# LC_Filter.net
KiCad netlist of a schematic drawn in EAGLE
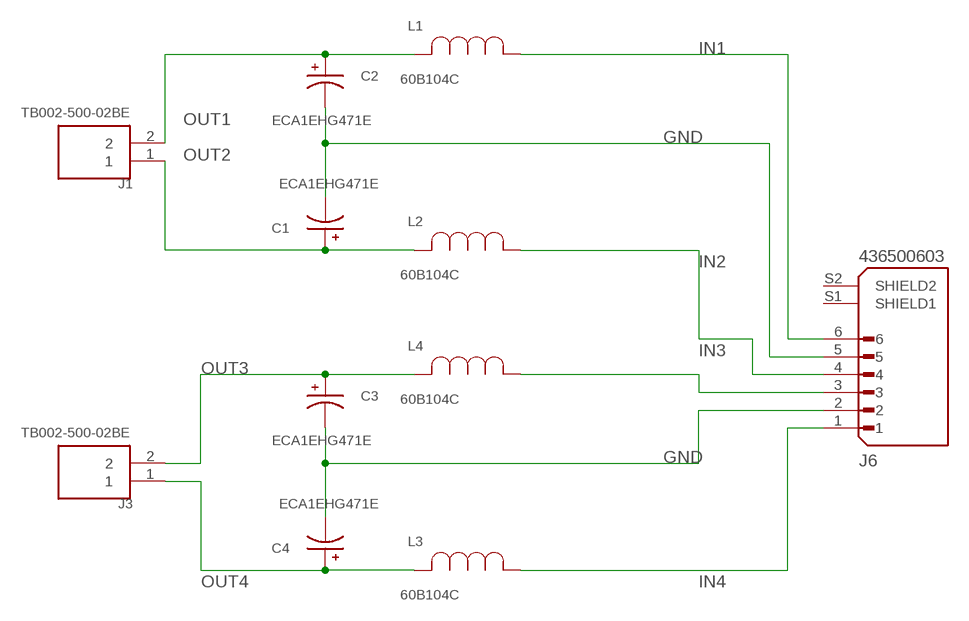
[diagram p0: schematic, sheet 1]

(export (version "E")
  (design (tool "Eeschema 10.0.6"))
  (components
    (comp (ref "C1")
      (value "ECA1EHG471E")
      (footprint "eagle-import:CAPPRD500W60D1000H1250")
      (fields (field (name "MF") "PANASONIC"))
      (libsource (lib "eagle-import") (part "ECA1EHG471E"))
    )
    (comp (ref "C2")
      (value "ECA1EHG471E")
      (footprint "eagle-import:CAPPRD500W60D1000H1250")
      (fields (field (name "MF") "PANASONIC"))
      (libsource (lib "eagle-import") (part "ECA1EHG471E"))
    )
    (comp (ref "C3")
      (value "ECA1EHG471E")
      (footprint "eagle-import:CAPPRD500W60D1000H1250")
      (fields (field (name "MF") "PANASONIC"))
      (libsource (lib "eagle-import") (part "ECA1EHG471E"))
    )
    (comp (ref "C4")
      (value "ECA1EHG471E")
      (footprint "eagle-import:CAPPRD500W60D1000H1250")
      (fields (field (name "MF") "PANASONIC"))
      (libsource (lib "eagle-import") (part "ECA1EHG471E"))
    )
    (comp (ref "J1")
      (value "TB002-500-02BE")
      (footprint "eagle-import:CUI_TB002-500-02BE")
      (fields (field (name "MANUFACTURER") "CUI"))
      (libsource (lib "eagle-import") (part "TB002-500-02BE"))
    )
    (comp (ref "J3")
      (value "TB002-500-02BE")
      (footprint "eagle-import:CUI_TB002-500-02BE")
      (fields (field (name "MANUFACTURER") "CUI"))
      (libsource (lib "eagle-import") (part "TB002-500-02BE"))
    )
    (comp (ref "J6")
      (value "436500603")
      (footprint "eagle-import:MOLEX_436500603")
      (fields (field (name "MANUFACTURER") "Molex"))
      (libsource (lib "eagle-import") (part "436500603"))
    )
    (comp (ref "L1")
      (value "60B104C")
      (footprint "eagle-import:6000B_SERIES_MUR")
      (fields (field (name "COPYRIGHT") "Copyright (C) 2022 Ultra Librarian. All rights reserved."))
      (libsource (lib "eagle-import") (part "60B104C"))
    )
    (comp (ref "L2")
      (value "60B104C")
      (footprint "eagle-import:6000B_SERIES_MUR")
      (fields (field (name "COPYRIGHT") "Copyright (C) 2022 Ultra Librarian. All rights reserved."))
      (libsource (lib "eagle-import") (part "60B104C"))
    )
    (comp (ref "L3")
      (value "60B104C")
      (footprint "eagle-import:6000B_SERIES_MUR")
      (fields (field (name "COPYRIGHT") "Copyright (C) 2022 Ultra Librarian. All rights reserved."))
      (libsource (lib "eagle-import") (part "60B104C"))
    )
    (comp (ref "L4")
      (value "60B104C")
      (footprint "eagle-import:6000B_SERIES_MUR")
      (fields (field (name "COPYRIGHT") "Copyright (C) 2022 Ultra Librarian. All rights reserved."))
      (libsource (lib "eagle-import") (part "60B104C"))
    )
  )
  (nets
    (net (code "1") (name "/GND") (class "Default")
      (node (ref "C1") (pin "N") (pinfunction "N_N") (pintype "passive"))
      (node (ref "C2") (pin "N") (pinfunction "N_N") (pintype "passive"))
      (node (ref "C3") (pin "N") (pinfunction "N_N") (pintype "passive"))
      (node (ref "C4") (pin "N") (pinfunction "N_N") (pintype "passive"))
      (node (ref "J6") (pin "2") (pinfunction "2_2") (pintype "passive"))
      (node (ref "J6") (pin "5") (pinfunction "5_5") (pintype "passive"))
    )
    (net (code "2") (name "/IN1") (class "Default")
      (node (ref "J6") (pin "6") (pinfunction "6_6") (pintype "passive"))
      (node (ref "L1") (pin "1") (pinfunction "1_1") (pintype "passive"))
    )
    (net (code "3") (name "/IN2") (class "Default")
      (node (ref "J6") (pin "4") (pinfunction "4_4") (pintype "passive"))
      (node (ref "L2") (pin "1") (pinfunction "1_1") (pintype "passive"))
    )
    (net (code "4") (name "/IN3") (class "Default")
      (node (ref "J6") (pin "3") (pinfunction "3_3") (pintype "passive"))
      (node (ref "L4") (pin "1") (pinfunction "1_1") (pintype "passive"))
    )
    (net (code "5") (name "/IN4") (class "Default")
      (node (ref "J6") (pin "1") (pinfunction "1_1") (pintype "passive"))
      (node (ref "L3") (pin "1") (pinfunction "1_1") (pintype "passive"))
    )
    (net (code "6") (name "/OUT1") (class "Default")
      (node (ref "C2") (pin "P") (pinfunction "P_P") (pintype "passive"))
      (node (ref "J1") (pin "2") (pinfunction "2_2") (pintype "passive"))
      (node (ref "L1") (pin "2") (pinfunction "2_2") (pintype "passive"))
    )
    (net (code "7") (name "/OUT2") (class "Default")
      (node (ref "C1") (pin "P") (pinfunction "P_P") (pintype "passive"))
      (node (ref "J1") (pin "1") (pinfunction "1_1") (pintype "passive"))
      (node (ref "L2") (pin "2") (pinfunction "2_2") (pintype "passive"))
    )
    (net (code "8") (name "/OUT3") (class "Default")
      (node (ref "C3") (pin "P") (pinfunction "P_P") (pintype "passive"))
      (node (ref "J3") (pin "2") (pinfunction "2_2") (pintype "passive"))
      (node (ref "L4") (pin "2") (pinfunction "2_2") (pintype "passive"))
    )
    (net (code "9") (name "/OUT4") (class "Default")
      (node (ref "C4") (pin "P") (pinfunction "P_P") (pintype "passive"))
      (node (ref "J3") (pin "1") (pinfunction "1_1") (pintype "passive"))
      (node (ref "L3") (pin "2") (pinfunction "2_2") (pintype "passive"))
    )
    (net (code "10") (name "unconnected-(J6-SHIELD1-PadS1)") (class "Default")
      (node (ref "J6") (pin "S1") (pinfunction "SHIELD1_S1") (pintype "passive"))
    )
    (net (code "11") (name "unconnected-(J6-SHIELD2-PadS2)") (class "Default")
      (node (ref "J6") (pin "S2") (pinfunction "SHIELD2_S2") (pintype "passive"))
    )
  )
)
